# PowerDetector.net
KiCad netlist of a schematic drawn in Altium Designer
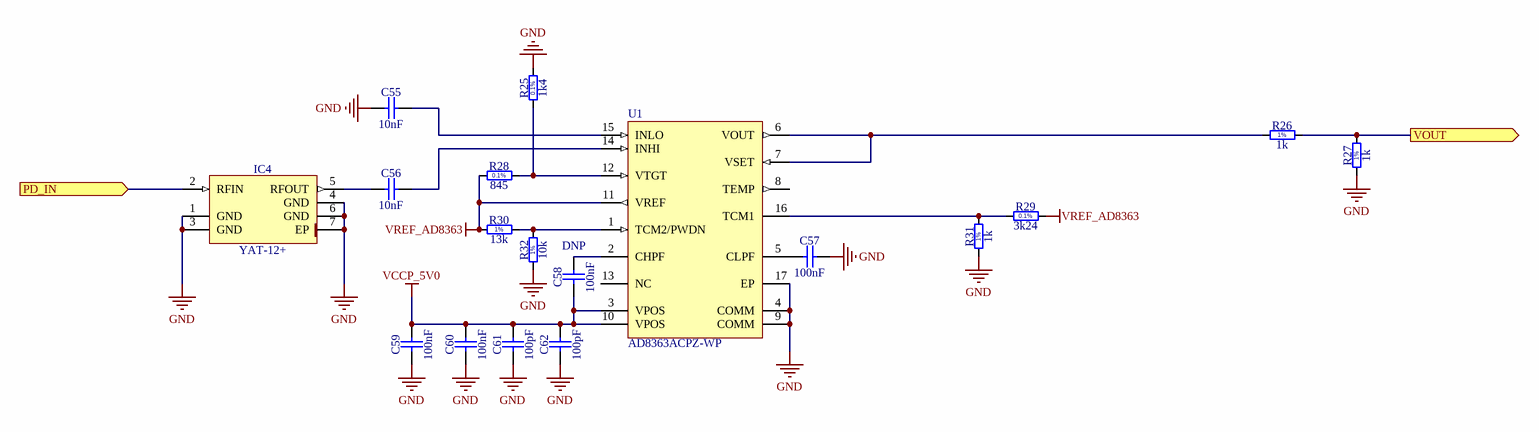
[diagram p0: PowerDetector.SchDoc]

(export (version "E")
  (design (tool "Eeschema 10.0.6"))
  (components
    (comp (ref "C55")
      (value "10nF")
      (footprint "CAPC1005X55N")
      (description "Non-polarised capacitor")
      (fields
        (field (name "PART NUMBER") "CC0402_10NF_16V_10%_X7R")
        (field (name "VOLTAGE") "16V")
        (field (name "AUTHOR") "CERN DEM JLC")
      )
      (libsource (lib "Capacitors") (part "Capacitor - non polarized"))
    )
    (comp (ref "C56")
      (value "10nF")
      (footprint "CAPC1005X55N")
      (description "Non-polarised capacitor")
      (fields
        (field (name "PART NUMBER") "CC0402_10NF_16V_10%_X7R")
        (field (name "VOLTAGE") "16V")
        (field (name "AUTHOR") "CERN DEM JLC")
      )
      (libsource (lib "Capacitors") (part "Capacitor - non polarized"))
    )
    (comp (ref "C57")
      (value "100nF")
      (footprint "CAPC1005X55N")
      (description "Non-polarised capacitor")
      (fields
        (field (name "PART NUMBER") "CC0402_100NF_16V_10%_X5R")
        (field (name "VOLTAGE") "16V")
        (field (name "AUTHOR") "CERN DEM JLC")
      )
      (libsource (lib "Capacitors") (part "Capacitor - non polarized"))
    )
    (comp (ref "C58")
      (value "100nF")
      (footprint "CAPC1005X55N")
      (description "Non-polarised capacitor")
      (fields
        (field (name "PART NUMBER") "CC0402_100NF_16V_10%_X5R")
        (field (name "VOLTAGE") "16V")
        (field (name "MOUNTED") "DNP")
        (field (name "AUTHOR") "CERN DEM JLC")
      )
      (libsource (lib "Capacitors") (part "Capacitor - non polarized"))
    )
    (comp (ref "C59")
      (value "100nF")
      (footprint "CAPC1005X55N")
      (description "Non-polarised capacitor")
      (fields
        (field (name "PART NUMBER") "CC0402_100NF_16V_10%_X5R")
        (field (name "VOLTAGE") "16V")
        (field (name "AUTHOR") "CERN DEM JLC")
      )
      (libsource (lib "Capacitors") (part "Capacitor - non polarized"))
    )
    (comp (ref "C60")
      (value "100nF")
      (footprint "CAPC1005X55N")
      (description "Non-polarised capacitor")
      (fields
        (field (name "PART NUMBER") "CC0402_100NF_16V_10%_X5R")
        (field (name "VOLTAGE") "16V")
        (field (name "AUTHOR") "CERN DEM JLC")
      )
      (libsource (lib "Capacitors") (part "Capacitor - non polarized"))
    )
    (comp (ref "C61")
      (value "100pF")
      (footprint "CAPC1005X55N")
      (description "Non-polarised capacitor")
      (fields
        (field (name "PART NUMBER") "CC0402_100PF_50V_5%_C0G")
        (field (name "VOLTAGE") "50V")
        (field (name "AUTHOR") "CERN DEM JLC")
      )
      (libsource (lib "Capacitors") (part "Capacitor - non polarized"))
    )
    (comp (ref "C62")
      (value "100pF")
      (footprint "CAPC1005X55N")
      (description "Non-polarised capacitor")
      (fields
        (field (name "PART NUMBER") "CC0402_100PF_50V_5%_C0G")
        (field (name "VOLTAGE") "50V")
        (field (name "AUTHOR") "CERN DEM JLC")
      )
      (libsource (lib "Capacitors") (part "Capacitor - non polarized"))
    )
    (comp (ref "IC4")
      (value "YAT-12+")
      (footprint "MINI-CIRCUITS_MC1630")
      (description "DC to 18GHz, 2W, 50 Ohm, 4dB Attenuator")
      (fields (field (name "MANUFACTURER") "MINI-CIRCUITS") (field (name "AUTHOR") "CERN DEM JLC"))
      (libsource (lib "ICs And Semiconductors") (part "YAT-XX+"))
    )
    (comp (ref "R25")
      (value "1k4")
      (footprint "RESC1608X55N")
      (description "Resistor - 0.1%")
      (fields
        (field (name "PART NUMBER") "R0603_1K4_0.1%_0.063W_10PPM")
        (field (name "POWER") "0.063W")
        (field (name "AUTHOR") "CERN DEM JLC")
      )
      (libsource (lib "Resistors") (part "Resistor - 0.1%"))
    )
    (comp (ref "R26")
      (value "1k")
      (footprint "RESC1005X40N")
      (description "Resistor - 1%")
      (fields
        (field (name "PART NUMBER") "R0402_1K_1%_0.0625W_100PPM")
        (field (name "POWER") "0.0625W")
        (field (name "AUTHOR") "CERN DEM JLC")
      )
      (libsource (lib "Resistors") (part "Resistor - 1%"))
    )
    (comp (ref "R27")
      (value "1k")
      (footprint "RESC1005X40N")
      (description "Resistor - 1%")
      (fields
        (field (name "PART NUMBER") "R0402_1K_1%_0.0625W_100PPM")
        (field (name "POWER") "0.0625W")
        (field (name "AUTHOR") "CERN DEM JLC")
      )
      (libsource (lib "Resistors") (part "Resistor - 1%"))
    )
    (comp (ref "R28")
      (value "845")
      (footprint "RESC1608X55N")
      (description "Resistor - 0.1%")
      (fields
        (field (name "PART NUMBER") "R0603_845R_0.1%_0.063W_10PPM")
        (field (name "POWER") "0.063W")
        (field (name "AUTHOR") "CERN DEM JLC")
      )
      (libsource (lib "Resistors") (part "Resistor - 0.1%"))
    )
    (comp (ref "R29")
      (value "3k24")
      (footprint "RESC1608X55N")
      (description "Resistor - 0.1%")
      (fields
        (field (name "PART NUMBER") "R0603_3K24_0.1%_0.063W_10PPM")
        (field (name "POWER") "0.063W")
        (field (name "AUTHOR") "CERN DEM JLC")
      )
      (libsource (lib "Resistors") (part "Resistor - 0.1%"))
    )
    (comp (ref "R30")
      (value "13k")
      (footprint "RESC1005X40N")
      (description "Resistor - 1%")
      (fields
        (field (name "PART NUMBER") "R0402_13K_1%_0.0625W_100PPM")
        (field (name "POWER") "0.0625W")
        (field (name "AUTHOR") "CERN DEM JLC")
      )
      (libsource (lib "Resistors") (part "Resistor - 1%"))
    )
    (comp (ref "R31")
      (value "1k")
      (footprint "RESC1005X40N")
      (description "Resistor - 1%")
      (fields
        (field (name "PART NUMBER") "R0402_1K_1%_0.0625W_100PPM")
        (field (name "POWER") "0.0625W")
        (field (name "AUTHOR") "CERN DEM JLC")
      )
      (libsource (lib "Resistors") (part "Resistor - 1%"))
    )
    (comp (ref "R32")
      (value "10k")
      (footprint "RESC1005X40N")
      (description "Resistor - 1%")
      (fields
        (field (name "PART NUMBER") "R0402_10K_1%_0.0625W_100PPM")
        (field (name "POWER") "0.0625W")
        (field (name "AUTHOR") "CERN DEM JLC")
      )
      (libsource (lib "Resistors") (part "Resistor - 1%"))
    )
    (comp (ref "U1")
      (value "AD8363ACPZ-WP")
      (footprint "ADI-CP-16-10_M")
      (description "50 Hz to 6 GHz,50 dB TruPwr™ Detector, 3µs Response Time, CP-16-10, Pb-Free, 64 Tray")
      (libsource (lib "Altium Content Vault") (part "ADI-AD8363-CP-16-10"))
    )
  )
  (nets
    (net (code "1") (name "/PD_IN") (class "Default")
      (node (ref "IC4") (pin "2") (pinfunction "RFIN_2") (pintype "input"))
    )
    (net (code "2") (name "/VOUT") (class "Default")
      (node (ref "R26") (pin "2") (pinfunction "2_2") (pintype "passive"))
      (node (ref "R27") (pin "2") (pinfunction "2_2") (pintype "passive"))
    )
    (net (code "3") (name "GND") (class "Default")
      (node (ref "C55") (pin "1") (pinfunction "1_1") (pintype "passive"))
      (node (ref "C57") (pin "2") (pinfunction "2_2") (pintype "passive"))
      (node (ref "C59") (pin "1") (pinfunction "1_1") (pintype "passive"))
      (node (ref "C60") (pin "1") (pinfunction "1_1") (pintype "passive"))
      (node (ref "C61") (pin "2") (pinfunction "2_2") (pintype "passive"))
      (node (ref "C62") (pin "2") (pinfunction "2_2") (pintype "passive"))
      (node (ref "IC4") (pin "1") (pinfunction "GND_1") (pintype "power_in"))
      (node (ref "IC4") (pin "3") (pinfunction "GND_3") (pintype "power_in"))
      (node (ref "IC4") (pin "4") (pinfunction "GND_4") (pintype "power_in"))
      (node (ref "IC4") (pin "6") (pinfunction "GND_6") (pintype "power_in"))
      (node (ref "IC4") (pin "7") (pinfunction "EP_7") (pintype "power_in"))
      (node (ref "R25") (pin "2") (pinfunction "2_2") (pintype "passive"))
      (node (ref "R27") (pin "1") (pinfunction "1_1") (pintype "passive"))
      (node (ref "R31") (pin "1") (pinfunction "1_1") (pintype "passive"))
      (node (ref "R32") (pin "1") (pinfunction "1_1") (pintype "passive"))
      (node (ref "U1") (pin "17") (pinfunction "EP_17") (pintype "power_in"))
      (node (ref "U1") (pin "4") (pinfunction "COMM_4") (pintype "power_in"))
      (node (ref "U1") (pin "9") (pinfunction "COMM_9") (pintype "power_in"))
    )
    (net (code "4") (name "Net-(IC4-RFOUT)") (class "Default")
      (node (ref "C56") (pin "1") (pinfunction "1_1") (pintype "passive"))
      (node (ref "IC4") (pin "5") (pinfunction "RFOUT_5") (pintype "output"))
    )
    (net (code "5") (name "Net-(U1-CHPF)") (class "Default")
      (node (ref "C58") (pin "2") (pinfunction "2_2") (pintype "passive"))
      (node (ref "U1") (pin "2") (pinfunction "CHPF_2") (pintype "passive"))
    )
    (net (code "6") (name "Net-(U1-CLPF)") (class "Default")
      (node (ref "C57") (pin "1") (pinfunction "1_1") (pintype "passive"))
      (node (ref "U1") (pin "5") (pinfunction "CLPF_5") (pintype "passive"))
    )
    (net (code "7") (name "Net-(U1-INHI)") (class "Default")
      (node (ref "C56") (pin "2") (pinfunction "2_2") (pintype "passive"))
      (node (ref "U1") (pin "14") (pinfunction "INHI_14") (pintype "input"))
    )
    (net (code "8") (name "Net-(U1-INLO)") (class "Default")
      (node (ref "C55") (pin "2") (pinfunction "2_2") (pintype "passive"))
      (node (ref "U1") (pin "15") (pinfunction "INLO_15") (pintype "input"))
    )
    (net (code "9") (name "Net-(U1-TCM1)") (class "Default")
      (node (ref "R29") (pin "1") (pinfunction "1_1") (pintype "passive"))
      (node (ref "R31") (pin "2") (pinfunction "2_2") (pintype "passive"))
      (node (ref "U1") (pin "16") (pinfunction "TCM1_16") (pintype "passive"))
    )
    (net (code "10") (name "Net-(U1-TCM2{slash}PWDN)") (class "Default")
      (node (ref "R30") (pin "2") (pinfunction "2_2") (pintype "passive"))
      (node (ref "R32") (pin "2") (pinfunction "2_2") (pintype "passive"))
      (node (ref "U1") (pin "1") (pinfunction "TCM2/PWDN_1") (pintype "input"))
    )
    (net (code "11") (name "Net-(U1-VOUT)") (class "Default")
      (node (ref "R26") (pin "1") (pinfunction "1_1") (pintype "passive"))
      (node (ref "U1") (pin "6") (pinfunction "VOUT_6") (pintype "output"))
      (node (ref "U1") (pin "7") (pinfunction "VSET_7") (pintype "input"))
    )
    (net (code "12") (name "Net-(U1-VTGT)") (class "Default")
      (node (ref "R25") (pin "1") (pinfunction "1_1") (pintype "passive"))
      (node (ref "R28") (pin "2") (pinfunction "2_2") (pintype "passive"))
      (node (ref "U1") (pin "12") (pinfunction "VTGT_12") (pintype "input"))
    )
    (net (code "13") (name "VCCP_5V0") (class "Default")
      (node (ref "C58") (pin "1") (pinfunction "1_1") (pintype "passive"))
      (node (ref "C59") (pin "2") (pinfunction "2_2") (pintype "passive"))
      (node (ref "C60") (pin "2") (pinfunction "2_2") (pintype "passive"))
      (node (ref "C61") (pin "1") (pinfunction "1_1") (pintype "passive"))
      (node (ref "C62") (pin "1") (pinfunction "1_1") (pintype "passive"))
      (node (ref "U1") (pin "10") (pinfunction "VPOS_10") (pintype "power_in"))
      (node (ref "U1") (pin "3") (pinfunction "VPOS_3") (pintype "power_in"))
    )
    (net (code "14") (name "VREF_AD8363") (class "Default")
      (node (ref "R28") (pin "1") (pinfunction "1_1") (pintype "passive"))
      (node (ref "R29") (pin "2") (pinfunction "2_2") (pintype "passive"))
      (node (ref "R30") (pin "1") (pinfunction "1_1") (pintype "passive"))
      (node (ref "U1") (pin "11") (pinfunction "VREF_11") (pintype "output"))
    )
    (net (code "15") (name "unconnected-(U1-NC-Pad13)") (class "Default")
      (node (ref "U1") (pin "13") (pinfunction "NC_13") (pintype "passive"))
    )
    (net (code "16") (name "unconnected-(U1-TEMP-Pad8)") (class "Default")
      (node (ref "U1") (pin "8") (pinfunction "TEMP_8") (pintype "output"))
    )
  )
)
